# DIYTIL311_Programmer.net
KiCad netlist of a schematic drawn in EAGLE
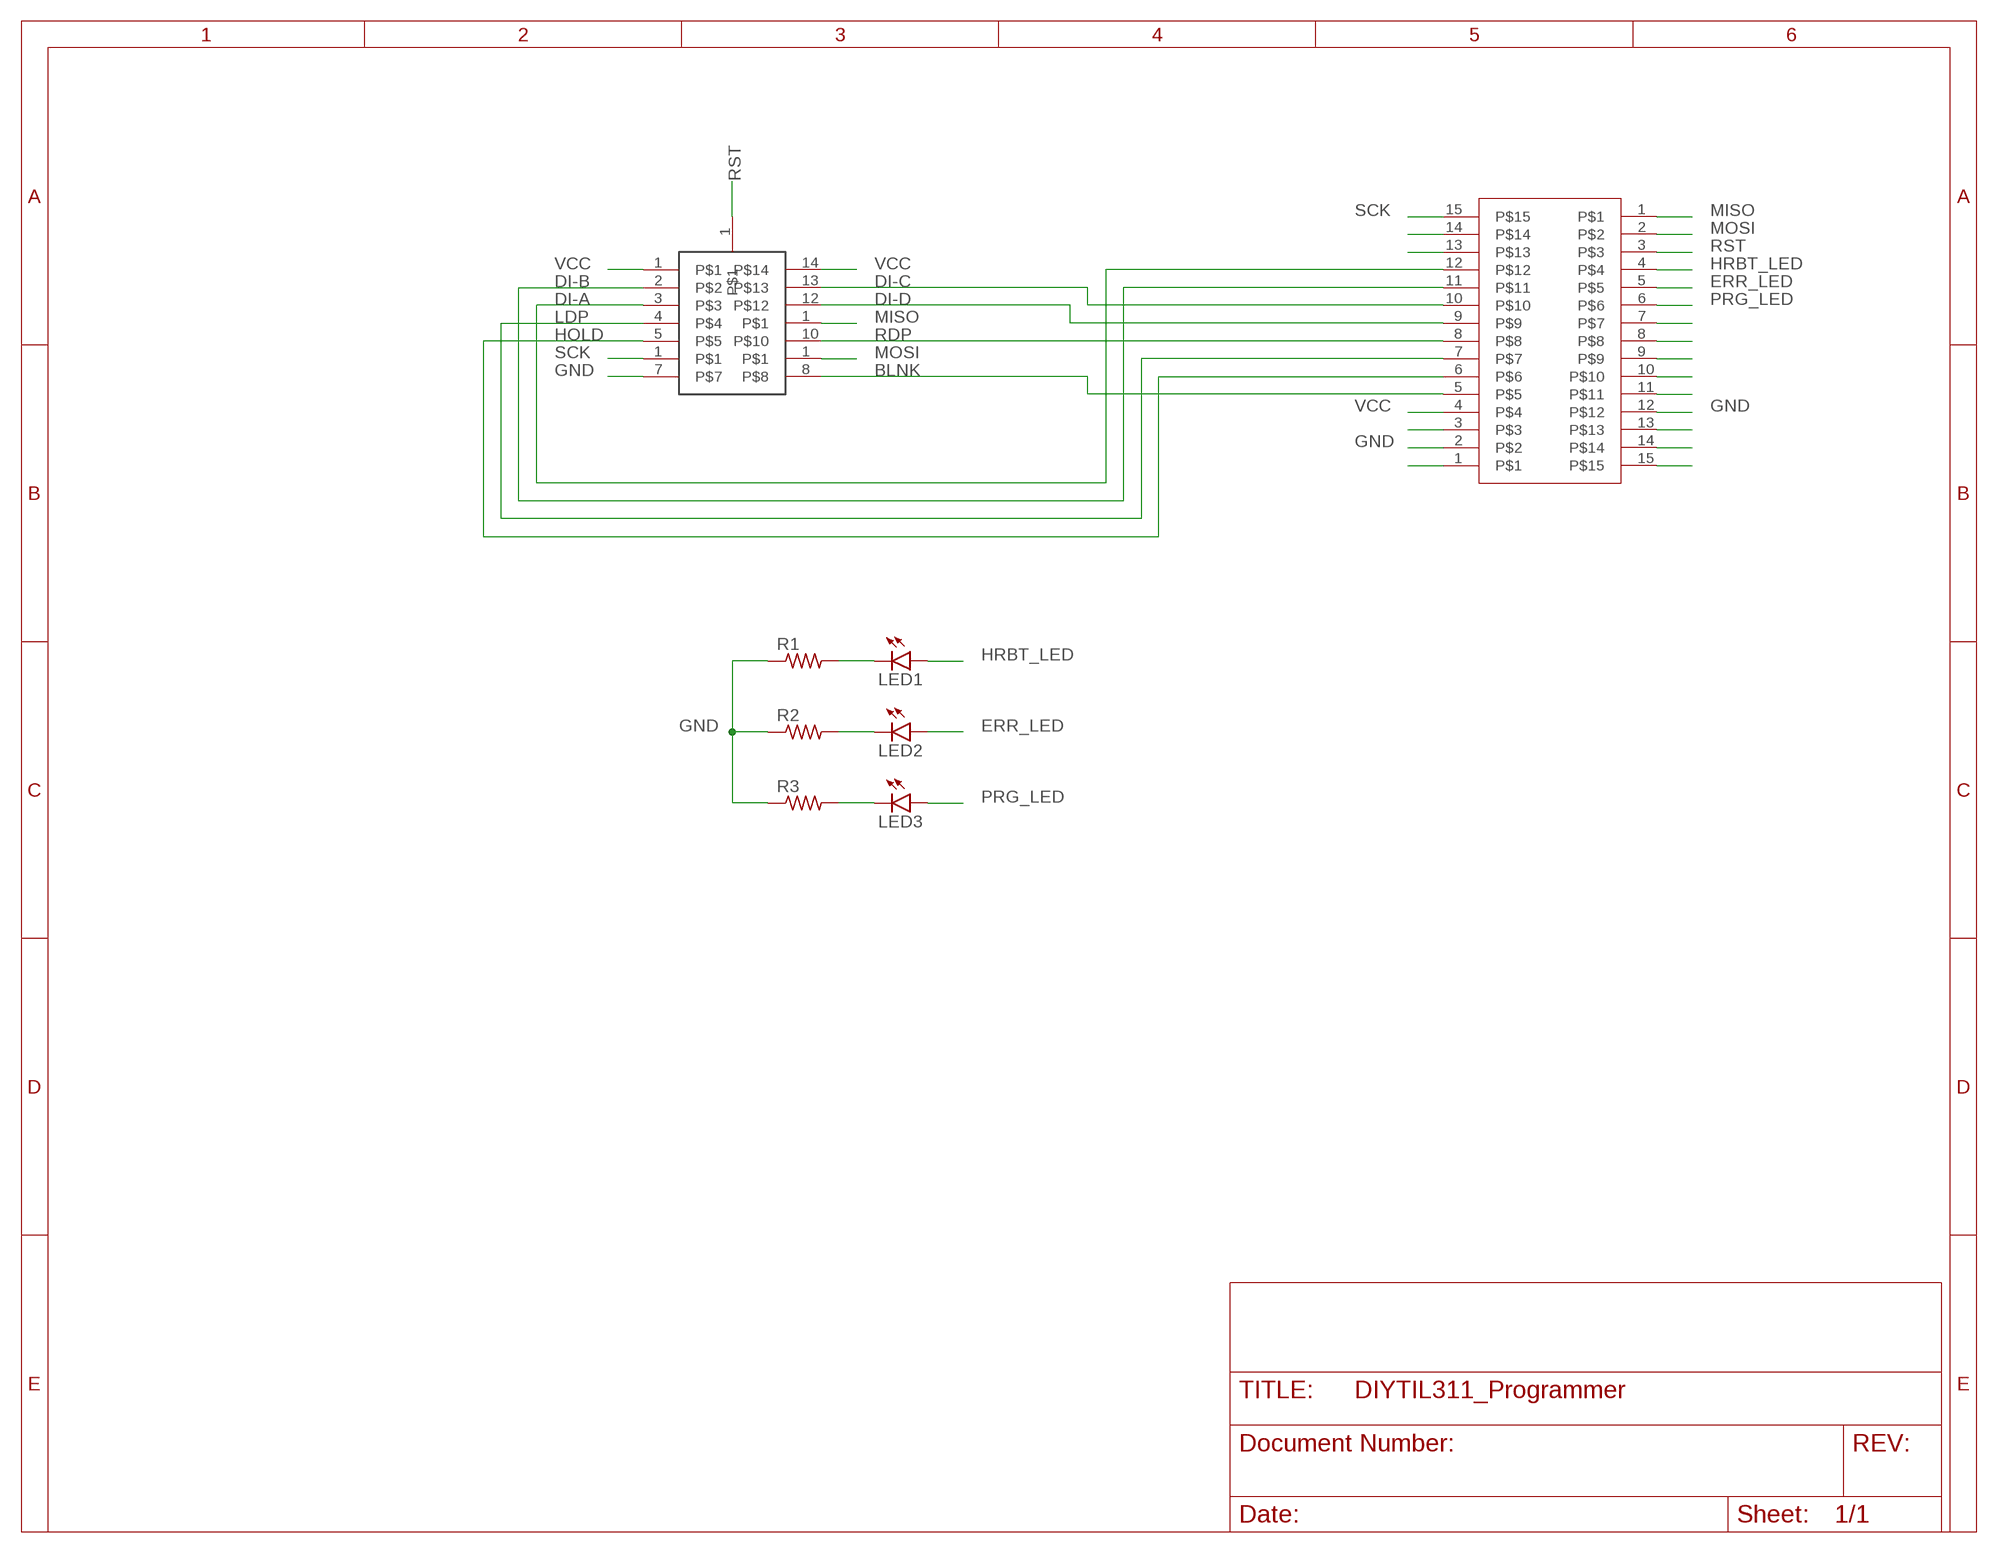
[diagram p0: schematic, sheet 1]

(export (version "E")
  (design (tool "Eeschema 10.0.6"))
  (components
    (comp (ref "LED1")
      (value "LED5MM")
      (footprint "eagle-import:LED5MM")
      (libsource (lib "eagle-import") (part "LED5MM"))
    )
    (comp (ref "LED2")
      (value "LED5MM")
      (footprint "eagle-import:LED5MM")
      (libsource (lib "eagle-import") (part "LED5MM"))
    )
    (comp (ref "LED3")
      (value "LED5MM")
      (footprint "eagle-import:LED5MM")
      (libsource (lib "eagle-import") (part "LED5MM"))
    )
    (comp (ref "MISO")
      (value "1X1_2.54MM1X1")
      (footprint "eagle-import:1X1_2.54MM_FOOTPRINT")
      (libsource (lib "eagle-import") (part "1X1_2.54MM1X1"))
    )
    (comp (ref "MOSI")
      (value "1X1_2.54MM1X1")
      (footprint "eagle-import:1X1_2.54MM_FOOTPRINT")
      (libsource (lib "eagle-import") (part "1X1_2.54MM1X1"))
    )
    (comp (ref "R1")
      (value "R-US_0204/7")
      (footprint "eagle-import:0204_7")
      (libsource (lib "eagle-import") (part "R-US_0204/7"))
    )
    (comp (ref "R2")
      (value "R-US_0204/7")
      (footprint "eagle-import:0204_7")
      (libsource (lib "eagle-import") (part "R-US_0204/7"))
    )
    (comp (ref "R3")
      (value "R-US_0204/7")
      (footprint "eagle-import:0204_7")
      (libsource (lib "eagle-import") (part "R-US_0204/7"))
    )
    (comp (ref "RST")
      (value "1X1_2.54MM1X1")
      (footprint "eagle-import:1X1_2.54MM_FOOTPRINT")
      (libsource (lib "eagle-import") (part "1X1_2.54MM1X1"))
    )
    (comp (ref "SCK")
      (value "1X1_2.54MM1X1")
      (footprint "eagle-import:1X1_2.54MM_FOOTPRINT")
      (libsource (lib "eagle-import") (part "1X1_2.54MM1X1"))
    )
    (comp (ref "U$1")
      (value "TIL311DIP")
      (footprint "eagle-import:TIL311DIP_FOOTPRINT")
      (libsource (lib "eagle-import") (part "TIL311DIP"))
    )
    (comp (ref "U$2")
      (value "1X15_2.54MM1X15_2.54MM")
      (footprint "eagle-import:1X15_2.54MM_FOOTPRINT")
      (libsource (lib "eagle-import") (part "1X15_2.54MM1X15_2.54MM"))
    )
    (comp (ref "U$3")
      (value "1X15_2.54MM1X15_2.54MM")
      (footprint "eagle-import:1X15_2.54MM_FOOTPRINT")
      (libsource (lib "eagle-import") (part "1X15_2.54MM1X15_2.54MM"))
    )
  )
  (nets
    (net (code "1") (name "/BLNK") (class "Default")
      (node (ref "U$1") (pin "8") (pinfunction "P$8_8") (pintype "bidirectional"))
      (node (ref "U$2") (pin "5") (pinfunction "P$5_5") (pintype "bidirectional"))
    )
    (net (code "2") (name "/DI-A") (class "Default")
      (node (ref "U$1") (pin "3") (pinfunction "P$3_3") (pintype "bidirectional"))
      (node (ref "U$2") (pin "12") (pinfunction "P$12_12") (pintype "bidirectional"))
    )
    (net (code "3") (name "/DI-B") (class "Default")
      (node (ref "U$1") (pin "2") (pinfunction "P$2_2") (pintype "bidirectional"))
      (node (ref "U$2") (pin "11") (pinfunction "P$11_11") (pintype "bidirectional"))
    )
    (net (code "4") (name "/DI-C") (class "Default")
      (node (ref "U$1") (pin "13") (pinfunction "P$13_13") (pintype "bidirectional"))
      (node (ref "U$2") (pin "10") (pinfunction "P$10_10") (pintype "bidirectional"))
    )
    (net (code "5") (name "/DI-D") (class "Default")
      (node (ref "U$1") (pin "12") (pinfunction "P$12_12") (pintype "bidirectional"))
      (node (ref "U$2") (pin "9") (pinfunction "P$9_9") (pintype "bidirectional"))
    )
    (net (code "6") (name "/ERR_LED") (class "Default")
      (node (ref "LED2") (pin "A") (pinfunction "A_A") (pintype "passive"))
      (node (ref "U$3") (pin "5") (pinfunction "P$5_5") (pintype "bidirectional"))
    )
    (net (code "7") (name "/GND") (class "Default")
      (node (ref "R1") (pin "1") (pinfunction "1_1") (pintype "passive"))
      (node (ref "R2") (pin "1") (pinfunction "1_1") (pintype "passive"))
      (node (ref "R3") (pin "1") (pinfunction "1_1") (pintype "passive"))
      (node (ref "U$1") (pin "7") (pinfunction "P$7_7") (pintype "bidirectional"))
      (node (ref "U$2") (pin "2") (pinfunction "P$2_2") (pintype "bidirectional"))
      (node (ref "U$3") (pin "12") (pinfunction "P$12_12") (pintype "bidirectional"))
    )
    (net (code "8") (name "/HOLD") (class "Default")
      (node (ref "U$1") (pin "5") (pinfunction "P$5_5") (pintype "bidirectional"))
      (node (ref "U$2") (pin "6") (pinfunction "P$6_6") (pintype "bidirectional"))
    )
    (net (code "9") (name "/HRBT_LED") (class "Default")
      (node (ref "LED1") (pin "A") (pinfunction "A_A") (pintype "passive"))
      (node (ref "U$3") (pin "4") (pinfunction "P$4_4") (pintype "bidirectional"))
    )
    (net (code "10") (name "/LDP") (class "Default")
      (node (ref "U$1") (pin "4") (pinfunction "P$4_4") (pintype "bidirectional"))
      (node (ref "U$2") (pin "7") (pinfunction "P$7_7") (pintype "bidirectional"))
    )
    (net (code "11") (name "/MISO") (class "Default")
      (node (ref "MISO") (pin "1") (pinfunction "P$1_1") (pintype "bidirectional"))
      (node (ref "U$3") (pin "1") (pinfunction "P$1_1") (pintype "bidirectional"))
    )
    (net (code "12") (name "/MOSI") (class "Default")
      (node (ref "MOSI") (pin "1") (pinfunction "P$1_1") (pintype "bidirectional"))
      (node (ref "U$3") (pin "2") (pinfunction "P$2_2") (pintype "bidirectional"))
    )
    (net (code "13") (name "/PRG_LED") (class "Default")
      (node (ref "LED3") (pin "A") (pinfunction "A_A") (pintype "passive"))
      (node (ref "U$3") (pin "6") (pinfunction "P$6_6") (pintype "bidirectional"))
    )
    (net (code "14") (name "/RDP") (class "Default")
      (node (ref "U$1") (pin "10") (pinfunction "P$10_10") (pintype "bidirectional"))
      (node (ref "U$2") (pin "8") (pinfunction "P$8_8") (pintype "bidirectional"))
    )
    (net (code "15") (name "/RST") (class "Default")
      (node (ref "RST") (pin "1") (pinfunction "P$1_1") (pintype "bidirectional"))
      (node (ref "U$3") (pin "3") (pinfunction "P$3_3") (pintype "bidirectional"))
    )
    (net (code "16") (name "/SCK") (class "Default")
      (node (ref "SCK") (pin "1") (pinfunction "P$1_1") (pintype "bidirectional"))
      (node (ref "U$2") (pin "15") (pinfunction "P$15_15") (pintype "bidirectional"))
    )
    (net (code "17") (name "/VCC") (class "Default")
      (node (ref "U$1") (pin "1") (pinfunction "P$1_1") (pintype "bidirectional"))
      (node (ref "U$1") (pin "14") (pinfunction "P$14_14") (pintype "bidirectional"))
      (node (ref "U$2") (pin "4") (pinfunction "P$4_4") (pintype "bidirectional"))
    )
    (net (code "18") (name "Net-(LED1-C)") (class "Default")
      (node (ref "LED1") (pin "K") (pinfunction "C_K") (pintype "passive"))
      (node (ref "R1") (pin "2") (pinfunction "2_2") (pintype "passive"))
    )
    (net (code "19") (name "Net-(LED2-C)") (class "Default")
      (node (ref "LED2") (pin "K") (pinfunction "C_K") (pintype "passive"))
      (node (ref "R2") (pin "2") (pinfunction "2_2") (pintype "passive"))
    )
    (net (code "20") (name "Net-(LED3-C)") (class "Default")
      (node (ref "LED3") (pin "K") (pinfunction "C_K") (pintype "passive"))
      (node (ref "R3") (pin "2") (pinfunction "2_2") (pintype "passive"))
    )
    (net (code "21") (name "unconnected-(U$2-P$1-Pad1)") (class "Default")
      (node (ref "U$2") (pin "1") (pinfunction "P$1_1") (pintype "bidirectional"))
    )
    (net (code "22") (name "unconnected-(U$2-P$3-Pad3)") (class "Default")
      (node (ref "U$2") (pin "3") (pinfunction "P$3_3") (pintype "bidirectional"))
    )
    (net (code "23") (name "unconnected-(U$2-P$13-Pad13)") (class "Default")
      (node (ref "U$2") (pin "13") (pinfunction "P$13_13") (pintype "bidirectional"))
    )
    (net (code "24") (name "unconnected-(U$2-P$14-Pad14)") (class "Default")
      (node (ref "U$2") (pin "14") (pinfunction "P$14_14") (pintype "bidirectional"))
    )
    (net (code "25") (name "unconnected-(U$3-P$7-Pad7)") (class "Default")
      (node (ref "U$3") (pin "7") (pinfunction "P$7_7") (pintype "bidirectional"))
    )
    (net (code "26") (name "unconnected-(U$3-P$8-Pad8)") (class "Default")
      (node (ref "U$3") (pin "8") (pinfunction "P$8_8") (pintype "bidirectional"))
    )
    (net (code "27") (name "unconnected-(U$3-P$9-Pad9)") (class "Default")
      (node (ref "U$3") (pin "9") (pinfunction "P$9_9") (pintype "bidirectional"))
    )
    (net (code "28") (name "unconnected-(U$3-P$10-Pad10)") (class "Default")
      (node (ref "U$3") (pin "10") (pinfunction "P$10_10") (pintype "bidirectional"))
    )
    (net (code "29") (name "unconnected-(U$3-P$11-Pad11)") (class "Default")
      (node (ref "U$3") (pin "11") (pinfunction "P$11_11") (pintype "bidirectional"))
    )
    (net (code "30") (name "unconnected-(U$3-P$13-Pad13)") (class "Default")
      (node (ref "U$3") (pin "13") (pinfunction "P$13_13") (pintype "bidirectional"))
    )
    (net (code "31") (name "unconnected-(U$3-P$14-Pad14)") (class "Default")
      (node (ref "U$3") (pin "14") (pinfunction "P$14_14") (pintype "bidirectional"))
    )
    (net (code "32") (name "unconnected-(U$3-P$15-Pad15)") (class "Default")
      (node (ref "U$3") (pin "15") (pinfunction "P$15_15") (pintype "bidirectional"))
    )
  )
)
